# linux_module.net
KiCad netlist of a schematic drawn in Altium Designer
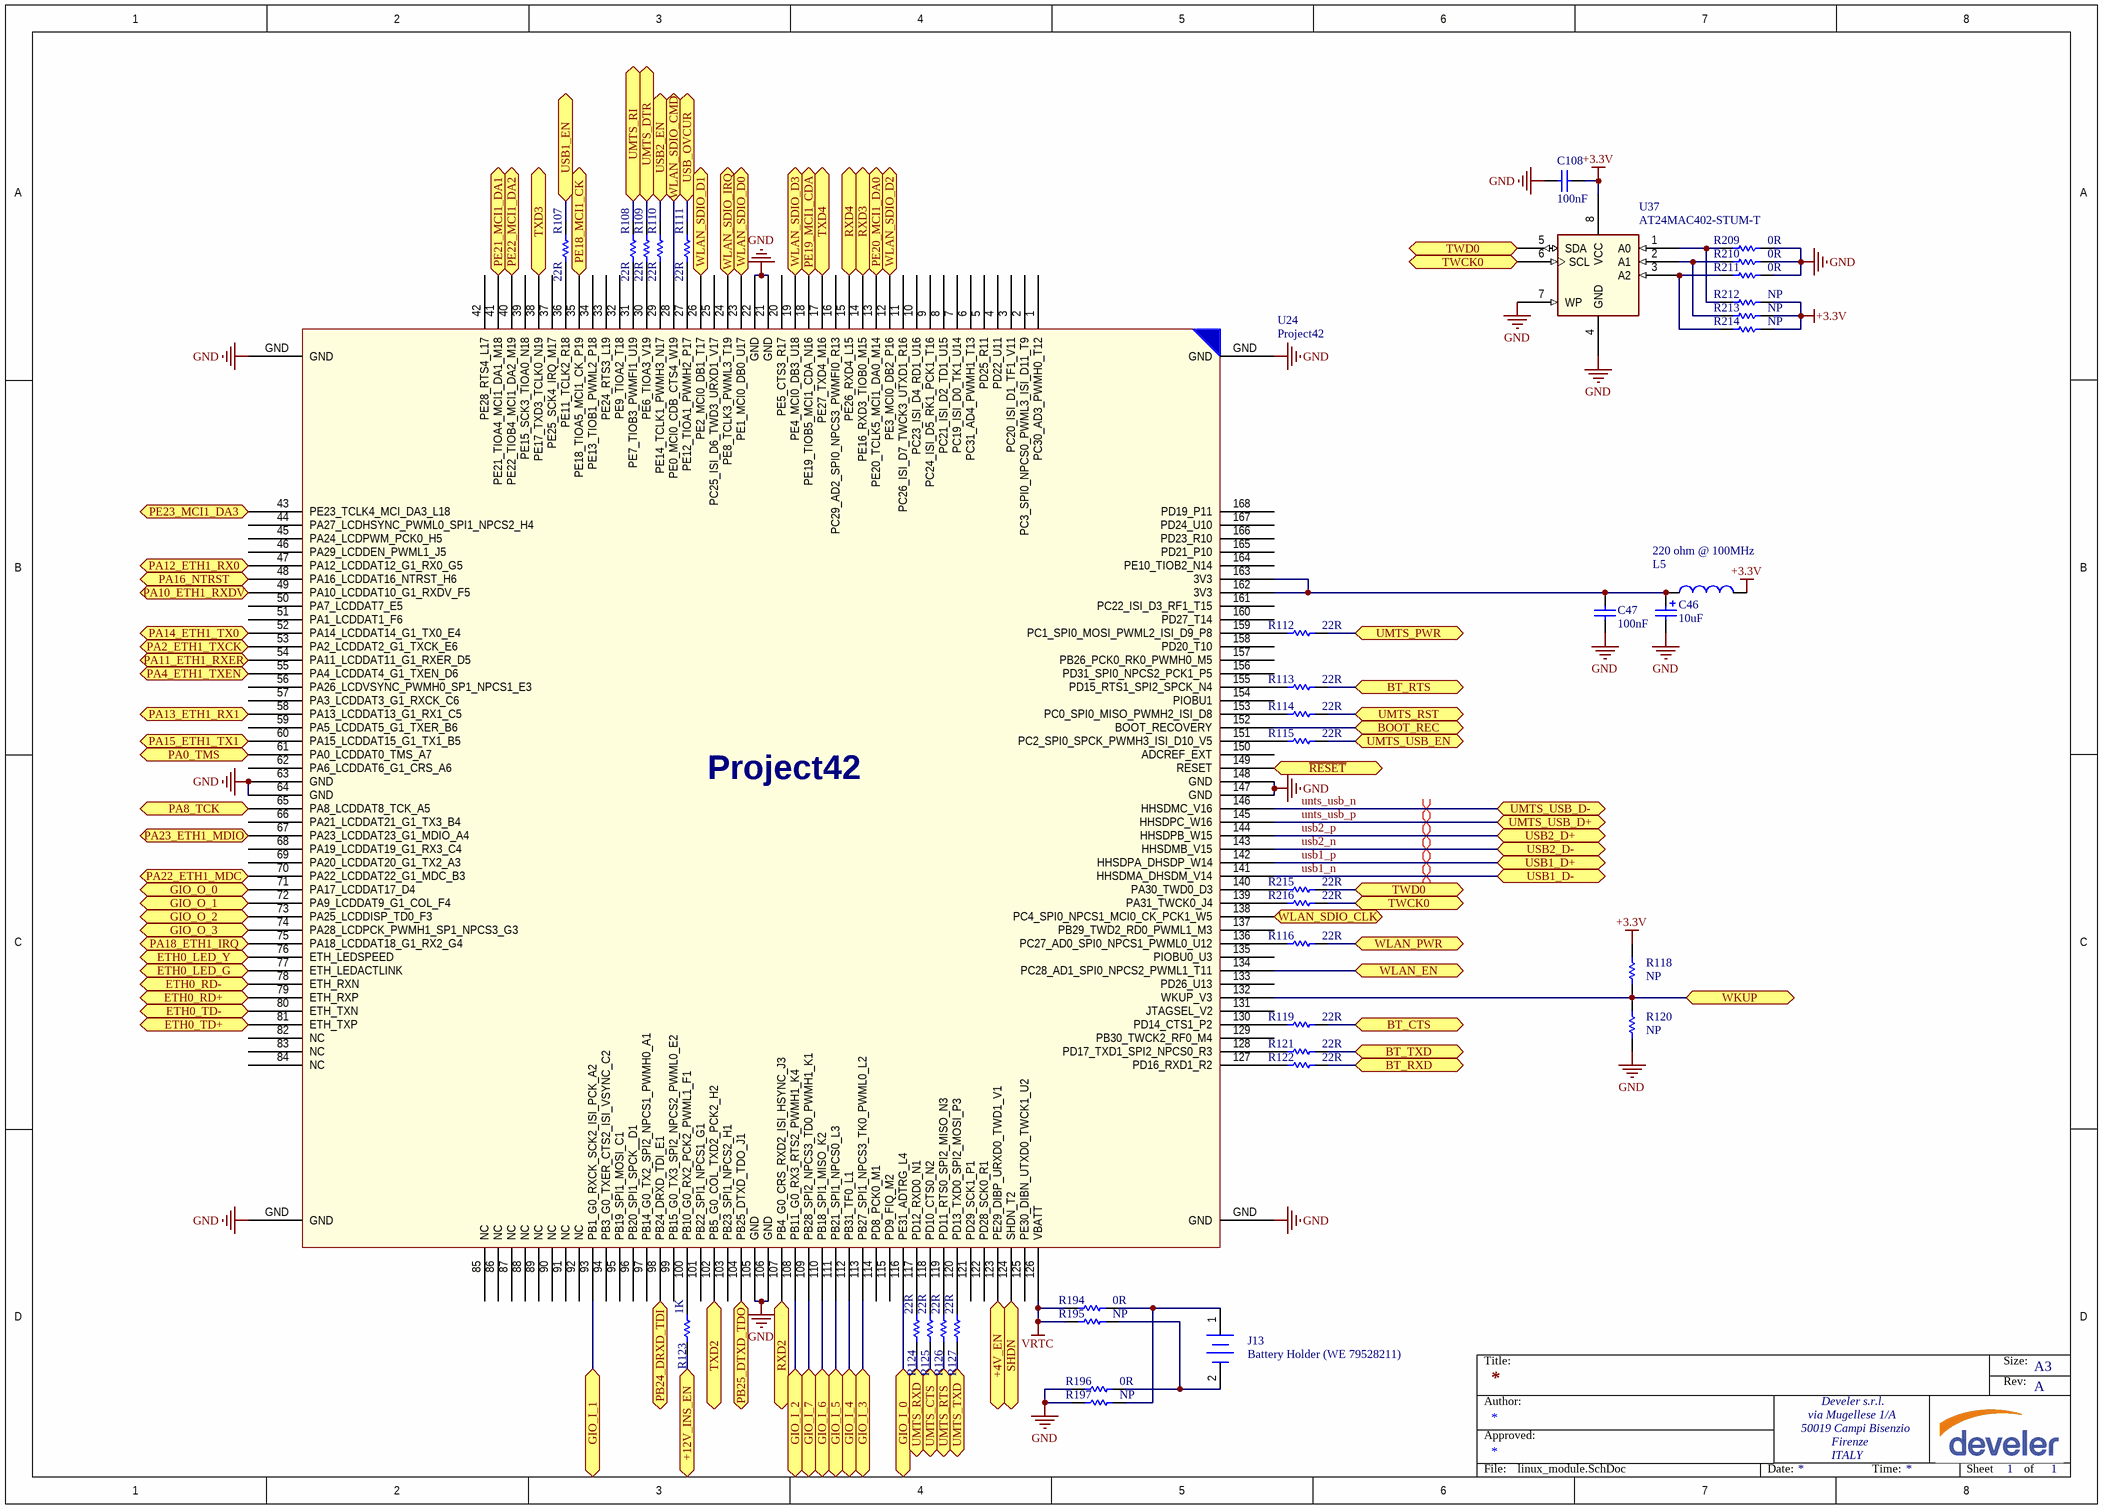
[diagram p0: linux_module.SchDoc]

(export (version "E")
  (design (tool "Eeschema 10.0.6"))
  (components
    (comp (ref "C46")
      (value "10uF")
      (footprint "1206_[3216]")
      (description "Ceramic X5R 25V")
      (fields (field (name "PUBLISHER") "Altium Limited"))
      (libsource (lib "DEVELER_Library") (part "Cap Pol1"))
    )
    (comp (ref "C47")
      (value "100nF")
      (footprint "0603_[1608]")
      (description "Ceramic X7R 50V")
      (fields (field (name "PUBLISHER") "Altium Limited"))
      (libsource (lib "Miscellaneous Devices") (part "Cap"))
    )
    (comp (ref "C108")
      (value "100nF")
      (footprint "0603_[1608]")
      (description "Ceramic X7R 50V")
      (fields (field (name "PUBLISHER") "Altium Limited"))
      (libsource (lib "Miscellaneous Devices") (part "Cap"))
    )
    (comp (ref "J13")
      (value "Battery Holder (WE 79528211)")
      (footprint "Battery_cr2032_holder")
      (description "Multicell Battery CR2032")
      (fields (field (name "PUBLISHER") "Altium Limited"))
      (libsource (lib "Miscellaneous Devices") (part "Battery"))
    )
    (comp (ref "L5")
      (value "220 ohm @ 100MHz")
      (footprint "0805_[2012]")
      (description "WE 742792022")
      (libsource (lib "DEVELER_Library") (part "Inductor"))
    )
    (comp (ref "R107")
      (value "22R")
      (footprint "0603_[1608]")
      (description "Resistor")
      (fields (field (name "PUBLISHER") "Altium Limited"))
      (libsource (lib "DEVELER_Library") (part "Res1"))
    )
    (comp (ref "R108")
      (value "22R")
      (footprint "0603_[1608]")
      (description "Resistor")
      (fields (field (name "PUBLISHER") "Altium Limited"))
      (libsource (lib "DEVELER_Library") (part "Res1"))
    )
    (comp (ref "R109")
      (value "22R")
      (footprint "0603_[1608]")
      (description "Resistor")
      (fields (field (name "PUBLISHER") "Altium Limited"))
      (libsource (lib "DEVELER_Library") (part "Res1"))
    )
    (comp (ref "R110")
      (value "22R")
      (footprint "0603_[1608]")
      (description "Resistor")
      (fields (field (name "PUBLISHER") "Altium Limited"))
      (libsource (lib "DEVELER_Library") (part "Res1"))
    )
    (comp (ref "R111")
      (value "22R")
      (footprint "0603_[1608]")
      (description "Resistor")
      (fields (field (name "PUBLISHER") "Altium Limited"))
      (libsource (lib "DEVELER_Library") (part "Res1"))
    )
    (comp (ref "R112")
      (value "22R")
      (footprint "0603_[1608]")
      (description "Resistor")
      (fields (field (name "PUBLISHER") "Altium Limited"))
      (libsource (lib "DEVELER_Library") (part "Res1"))
    )
    (comp (ref "R113")
      (value "22R")
      (footprint "0603_[1608]")
      (description "Resistor")
      (fields (field (name "PUBLISHER") "Altium Limited"))
      (libsource (lib "DEVELER_Library") (part "Res1"))
    )
    (comp (ref "R114")
      (value "22R")
      (footprint "0603_[1608]")
      (description "Resistor")
      (fields (field (name "PUBLISHER") "Altium Limited"))
      (libsource (lib "DEVELER_Library") (part "Res1"))
    )
    (comp (ref "R115")
      (value "22R")
      (footprint "0603_[1608]")
      (description "Resistor")
      (fields (field (name "PUBLISHER") "Altium Limited"))
      (libsource (lib "DEVELER_Library") (part "Res1"))
    )
    (comp (ref "R116")
      (value "22R")
      (footprint "0603_[1608]")
      (description "Resistor")
      (fields (field (name "PUBLISHER") "Altium Limited"))
      (libsource (lib "DEVELER_Library") (part "Res1"))
    )
    (comp (ref "R118")
      (value "NP")
      (footprint "0603_[1608]")
      (description "Resistor")
      (fields (field (name "PUBLISHER") "Altium Limited"))
      (libsource (lib "DEVELER_Library") (part "Res1"))
    )
    (comp (ref "R119")
      (value "22R")
      (footprint "0603_[1608]")
      (description "Resistor")
      (fields (field (name "PUBLISHER") "Altium Limited"))
      (libsource (lib "DEVELER_Library") (part "Res1"))
    )
    (comp (ref "R120")
      (value "NP")
      (footprint "0603_[1608]")
      (description "Resistor")
      (fields (field (name "PUBLISHER") "Altium Limited"))
      (libsource (lib "DEVELER_Library") (part "Res1"))
    )
    (comp (ref "R121")
      (value "22R")
      (footprint "0603_[1608]")
      (description "Resistor")
      (fields (field (name "PUBLISHER") "Altium Limited"))
      (libsource (lib "DEVELER_Library") (part "Res1"))
    )
    (comp (ref "R122")
      (value "22R")
      (footprint "0603_[1608]")
      (description "Resistor")
      (fields (field (name "PUBLISHER") "Altium Limited"))
      (libsource (lib "DEVELER_Library") (part "Res1"))
    )
    (comp (ref "R123")
      (value "1K")
      (footprint "0603_[1608]")
      (description "Resistor")
      (fields (field (name "PUBLISHER") "Altium Limited"))
      (libsource (lib "DEVELER_Library") (part "Res1"))
    )
    (comp (ref "R124")
      (value "22R")
      (footprint "0603_[1608]")
      (description "Resistor")
      (fields (field (name "PUBLISHER") "Altium Limited"))
      (libsource (lib "DEVELER_Library") (part "Res1"))
    )
    (comp (ref "R125")
      (value "22R")
      (footprint "0603_[1608]")
      (description "Resistor")
      (fields (field (name "PUBLISHER") "Altium Limited"))
      (libsource (lib "DEVELER_Library") (part "Res1"))
    )
    (comp (ref "R126")
      (value "22R")
      (footprint "0603_[1608]")
      (description "Resistor")
      (fields (field (name "PUBLISHER") "Altium Limited"))
      (libsource (lib "DEVELER_Library") (part "Res1"))
    )
    (comp (ref "R127")
      (value "22R")
      (footprint "0603_[1608]")
      (description "Resistor")
      (fields (field (name "PUBLISHER") "Altium Limited"))
      (libsource (lib "DEVELER_Library") (part "Res1"))
    )
    (comp (ref "R194")
      (value "0R")
      (footprint "0603_[1608]")
      (description "Resistor")
      (fields (field (name "PUBLISHER") "Altium Limited"))
      (libsource (lib "DEVELER_Library") (part "Res1"))
    )
    (comp (ref "R195")
      (value "NP")
      (footprint "0603_[1608]")
      (description "Resistor")
      (fields (field (name "PUBLISHER") "Altium Limited"))
      (libsource (lib "DEVELER_Library") (part "Res1"))
    )
    (comp (ref "R196")
      (value "0R")
      (footprint "0603_[1608]")
      (description "Resistor")
      (fields (field (name "PUBLISHER") "Altium Limited"))
      (libsource (lib "DEVELER_Library") (part "Res1"))
    )
    (comp (ref "R197")
      (value "NP")
      (footprint "0603_[1608]")
      (description "Resistor")
      (fields (field (name "PUBLISHER") "Altium Limited"))
      (libsource (lib "DEVELER_Library") (part "Res1"))
    )
    (comp (ref "R209")
      (value "0R")
      (footprint "0603_[1608]")
      (description "Resistor")
      (fields (field (name "PUBLISHER") "Altium Limited"))
      (libsource (lib "DEVELER_Library") (part "Res1"))
    )
    (comp (ref "R210")
      (value "0R")
      (footprint "0603_[1608]")
      (description "Resistor")
      (fields (field (name "PUBLISHER") "Altium Limited"))
      (libsource (lib "DEVELER_Library") (part "Res1"))
    )
    (comp (ref "R211")
      (value "0R")
      (footprint "0603_[1608]")
      (description "Resistor")
      (fields (field (name "PUBLISHER") "Altium Limited"))
      (libsource (lib "DEVELER_Library") (part "Res1"))
    )
    (comp (ref "R212")
      (value "NP")
      (footprint "0603_[1608]")
      (description "Resistor")
      (fields (field (name "PUBLISHER") "Altium Limited"))
      (libsource (lib "DEVELER_Library") (part "Res1"))
    )
    (comp (ref "R213")
      (value "NP")
      (footprint "0603_[1608]")
      (description "Resistor")
      (fields (field (name "PUBLISHER") "Altium Limited"))
      (libsource (lib "DEVELER_Library") (part "Res1"))
    )
    (comp (ref "R214")
      (value "NP")
      (footprint "0603_[1608]")
      (description "Resistor")
      (fields (field (name "PUBLISHER") "Altium Limited"))
      (libsource (lib "DEVELER_Library") (part "Res1"))
    )
    (comp (ref "R215")
      (value "22R")
      (footprint "0603_[1608]")
      (description "Resistor")
      (fields (field (name "PUBLISHER") "Altium Limited"))
      (libsource (lib "DEVELER_Library") (part "Res1"))
    )
    (comp (ref "R216")
      (value "22R")
      (footprint "0603_[1608]")
      (description "Resistor")
      (fields (field (name "PUBLISHER") "Altium Limited"))
      (libsource (lib "DEVELER_Library") (part "Res1"))
    )
    (comp (ref "U24")
      (value "Project42")
      (footprint "project42_footprint")
      (description "Faster Little Linux Module")
      (libsource (lib "project42_lib") (part "project42_pinout"))
    )
    (comp (ref "U37")
      (value "AT24MAC402-STUM-T")
      (footprint "SOIC8")
      (description "EEPROM MAC 48bit EUI + Serial (AT24MAC602-STUM-T for 64bit EUI)")
      (libsource (lib "DEVELER_Library") (part "EEPROM-SOIC8"))
    )
  )
  (nets
    (net (code "1") (name "+3.3V") (class "Default")
      (node (ref "C108") (pin "1") (pinfunction "1_1") (pintype "passive"))
      (node (ref "L5") (pin "1") (pinfunction "1_1") (pintype "passive"))
      (node (ref "R118") (pin "2") (pinfunction "2_2") (pintype "passive"))
      (node (ref "R212") (pin "1") (pinfunction "1_1") (pintype "passive"))
      (node (ref "R213") (pin "1") (pinfunction "1_1") (pintype "passive"))
      (node (ref "R214") (pin "1") (pinfunction "1_1") (pintype "passive"))
      (node (ref "U37") (pin "8") (pinfunction "VCC_8") (pintype "power_in"))
    )
    (net (code "2") (name "/+4V_EN") (class "Default")
      (node (ref "U24") (pin "123") (pinfunction "PE29_DIBP_URXD0_TWD1_V1_123") (pintype "passive"))
    )
    (net (code "3") (name "/+12V_INS_EN") (class "Default")
      (node (ref "R123") (pin "1") (pinfunction "1_1") (pintype "passive"))
    )
    (net (code "4") (name "/BOOT_REC") (class "Default")
      (node (ref "U24") (pin "152") (pinfunction "BOOT_RECOVERY_152") (pintype "passive"))
    )
    (net (code "5") (name "/BT_CTS") (class "Default")
      (node (ref "R119") (pin "1") (pinfunction "1_1") (pintype "passive"))
    )
    (net (code "6") (name "/BT_RTS") (class "Default")
      (node (ref "R113") (pin "1") (pinfunction "1_1") (pintype "passive"))
    )
    (net (code "7") (name "/BT_RXD") (class "Default")
      (node (ref "R122") (pin "1") (pinfunction "1_1") (pintype "passive"))
    )
    (net (code "8") (name "/BT_TXD") (class "Default")
      (node (ref "R121") (pin "1") (pinfunction "1_1") (pintype "passive"))
    )
    (net (code "9") (name "/ETH0_LED_G") (class "Default")
      (node (ref "U24") (pin "77") (pinfunction "ETH_LEDACTLINK_77") (pintype "passive"))
    )
    (net (code "10") (name "/ETH0_LED_Y") (class "Default")
      (node (ref "U24") (pin "76") (pinfunction "ETH_LEDSPEED_76") (pintype "passive"))
    )
    (net (code "11") (name "/ETH0_RD+") (class "Default")
      (node (ref "U24") (pin "79") (pinfunction "ETH_RXP_79") (pintype "passive"))
    )
    (net (code "12") (name "/ETH0_RD-") (class "Default")
      (node (ref "U24") (pin "78") (pinfunction "ETH_RXN_78") (pintype "passive"))
    )
    (net (code "13") (name "/ETH0_TD+") (class "Default")
      (node (ref "U24") (pin "81") (pinfunction "ETH_TXP_81") (pintype "passive"))
    )
    (net (code "14") (name "/ETH0_TD-") (class "Default")
      (node (ref "U24") (pin "80") (pinfunction "ETH_TXN_80") (pintype "passive"))
    )
    (net (code "15") (name "/GIO_I_0") (class "Default")
      (node (ref "U24") (pin "116") (pinfunction "PE31_ADTRG_L4_116") (pintype "passive"))
    )
    (net (code "16") (name "/GIO_I_1") (class "Default")
      (node (ref "U24") (pin "93") (pinfunction "PB1_G0_RXCK_SCK2_ISI_PCK_A2_93") (pintype "passive"))
    )
    (net (code "17") (name "/GIO_I_2") (class "Default")
      (node (ref "U24") (pin "108") (pinfunction "PB11_G0_RX3_RTS2_PWMH1_K4_108") (pintype "passive"))
    )
    (net (code "18") (name "/GIO_I_3") (class "Default")
      (node (ref "U24") (pin "113") (pinfunction "PB27_SPI1_NPCS3_TK0_PWML0_L2_113") (pintype "passive"))
    )
    (net (code "19") (name "/GIO_I_4") (class "Default")
      (node (ref "U24") (pin "112") (pinfunction "PB31_TF0_L1_112") (pintype "passive"))
    )
    (net (code "20") (name "/GIO_I_5") (class "Default")
      (node (ref "U24") (pin "111") (pinfunction "PB21_SPI1_NPCS0_L3_111") (pintype "passive"))
    )
    (net (code "21") (name "/GIO_I_6") (class "Default")
      (node (ref "U24") (pin "110") (pinfunction "PB18_SPI1_MISO_K2_110") (pintype "passive"))
    )
    (net (code "22") (name "/GIO_I_7") (class "Default")
      (node (ref "U24") (pin "109") (pinfunction "PB28_SPI2_NPCS3_TD0_PWMH1_K1_109") (pintype "passive"))
    )
    (net (code "23") (name "/GIO_O_0") (class "Default")
      (node (ref "U24") (pin "71") (pinfunction "PA17_LCDDAT17_D4_71") (pintype "passive"))
    )
    (net (code "24") (name "/GIO_O_1") (class "Default")
      (node (ref "U24") (pin "72") (pinfunction "PA9_LCDDAT9_G1_COL_F4_72") (pintype "passive"))
    )
    (net (code "25") (name "/GIO_O_2") (class "Default")
      (node (ref "U24") (pin "73") (pinfunction "PA25_LCDDISP_TD0_F3_73") (pintype "passive"))
    )
    (net (code "26") (name "/GIO_O_3") (class "Default")
      (node (ref "U24") (pin "74") (pinfunction "PA28_LCDPCK_PWMH1_SP1_NPCS3_G3_74") (pintype "passive"))
    )
    (net (code "27") (name "/PA0_TMS") (class "Default")
      (node (ref "U24") (pin "61") (pinfunction "PA0_LCDDAT0_TMS_A7_61") (pintype "passive"))
    )
    (net (code "28") (name "/PA2_ETH1_TXCK") (class "Default")
      (node (ref "U24") (pin "53") (pinfunction "PA2_LCDDAT2_G1_TXCK_E6_53") (pintype "passive"))
    )
    (net (code "29") (name "/PA4_ETH1_TXEN") (class "Default")
      (node (ref "U24") (pin "55") (pinfunction "PA4_LCDDAT4_G1_TXEN_D6_55") (pintype "passive"))
    )
    (net (code "30") (name "/PA8_TCK") (class "Default")
      (node (ref "U24") (pin "65") (pinfunction "PA8_LCDDAT8_TCK_A5_65") (pintype "passive"))
    )
    (net (code "31") (name "/PA10_ETH1_RXDV") (class "Default")
      (node (ref "U24") (pin "49") (pinfunction "PA10_LCDDAT10_G1_RXDV_F5_49") (pintype "passive"))
    )
    (net (code "32") (name "/PA11_ETH1_RXER") (class "Default")
      (node (ref "U24") (pin "54") (pinfunction "PA11_LCDDAT11_G1_RXER_D5_54") (pintype "passive"))
    )
    (net (code "33") (name "/PA12_ETH1_RX0") (class "Default")
      (node (ref "U24") (pin "47") (pinfunction "PA12_LCDDAT12_G1_RX0_G5_47") (pintype "passive"))
    )
    (net (code "34") (name "/PA13_ETH1_RX1") (class "Default")
      (node (ref "U24") (pin "58") (pinfunction "PA13_LCDDAT13_G1_RX1_C5_58") (pintype "passive"))
    )
    (net (code "35") (name "/PA14_ETH1_TX0") (class "Default")
      (node (ref "U24") (pin "52") (pinfunction "PA14_LCDDAT14_G1_TX0_E4_52") (pintype "passive"))
    )
    (net (code "36") (name "/PA15_ETH1_TX1") (class "Default")
      (node (ref "U24") (pin "60") (pinfunction "PA15_LCDDAT15_G1_TX1_B5_60") (pintype "passive"))
    )
    (net (code "37") (name "/PA16_NTRST") (class "Default")
      (node (ref "U24") (pin "48") (pinfunction "PA16_LCDDAT16_NTRST_H6_48") (pintype "passive"))
    )
    (net (code "38") (name "/PA18_ETH1_IRQ") (class "Default")
      (node (ref "U24") (pin "75") (pinfunction "PA18_LCDDAT18_G1_RX2_G4_75") (pintype "passive"))
    )
    (net (code "39") (name "/PA22_ETH1_MDC") (class "Default")
      (node (ref "U24") (pin "70") (pinfunction "PA22_LCDDAT22_G1_MDC_B3_70") (pintype "passive"))
    )
    (net (code "40") (name "/PA23_ETH1_MDIO") (class "Default")
      (node (ref "U24") (pin "67") (pinfunction "PA23_LCDDAT23_G1_MDIO_A4_67") (pintype "passive"))
    )
    (net (code "41") (name "/PB24_DRXD_TDI") (class "Default")
      (node (ref "U24") (pin "98") (pinfunction "PB24_DRXD_TDI_E1_98") (pintype "passive"))
    )
    (net (code "42") (name "/PB25_DTXD_TDO") (class "Default")
      (node (ref "U24") (pin "104") (pinfunction "PB25_DTXD_TDO_J1_104") (pintype "passive"))
    )
    (net (code "48") (name "/PE18_MCI1_CK") (class "Default")
      (node (ref "U24") (pin "35") (pinfunction "PE18_TIOA5_MCI1_CK_P19_35") (pintype "passive"))
    )
    (net (code "50") (name "/PE19_MCI1_CDA") (class "Default")
      (node (ref "U24") (pin "18") (pinfunction "PE19_TIOB5_MCI1_CDA_N16_18") (pintype "passive"))
    )
    (net (code "53") (name "/PE20_MCI1_DA0") (class "Default")
      (node (ref "U24") (pin "13") (pinfunction "PE20_TCLK5_MCI1_DA0_M14_13") (pintype "passive"))
    )
    (net (code "54") (name "/PE21_MCI1_DA1") (class "Default")
      (node (ref "U24") (pin "41") (pinfunction "PE21_TIOA4_MCI1_DA1_M18_41") (pintype "passive"))
    )
    (net (code "55") (name "/PE22_MCI1_DA2") (class "Default")
      (node (ref "U24") (pin "40") (pinfunction "PE22_TIOB4_MCI1_DA2_M19_40") (pintype "passive"))
    )
    (net (code "56") (name "/PE23_MCI1_DA3") (class "Default")
      (node (ref "U24") (pin "43") (pinfunction "PE23_TCLK4_MCI_DA3_L18_43") (pintype "passive"))
    )
    (net (code "59") (name "/RXD2") (class "Default")
      (node (ref "U24") (pin "107") (pinfunction "PB4_G0_CRS_RXD2_ISI_HSYNC_J3_107") (pintype "passive"))
    )
    (net (code "60") (name "/RXD3") (class "Default")
      (node (ref "U24") (pin "14") (pinfunction "PE16_RXD3_TIOB0_M15_14") (pintype "passive"))
    )
    (net (code "61") (name "/RXD4") (class "Default")
      (node (ref "U24") (pin "15") (pinfunction "PE26_RXD4_L15_15") (pintype "passive"))
    )
    (net (code "62") (name "/SHDN") (class "Default")
      (node (ref "U24") (pin "124") (pinfunction "SHDN_T2_124") (pintype "passive"))
    )
    (net (code "63") (name "/TWCK0") (class "Default")
      (node (ref "R216") (pin "1") (pinfunction "1_1") (pintype "passive"))
      (node (ref "U37") (pin "6") (pinfunction "SCL_6") (pintype "input"))
    )
    (net (code "64") (name "/TWD0") (class "Default")
      (node (ref "R215") (pin "1") (pinfunction "1_1") (pintype "passive"))
      (node (ref "U37") (pin "5") (pinfunction "SDA_5") (pintype "bidirectional"))
    )
    (net (code "65") (name "/TXD2") (class "Default")
      (node (ref "U24") (pin "102") (pinfunction "PB5_G0_COL_TXD2_PCK2_H2_102") (pintype "passive"))
    )
    (net (code "66") (name "/TXD3") (class "Default")
      (node (ref "U24") (pin "38") (pinfunction "PE17_TXD3_TCLK0_N19_38") (pintype "passive"))
    )
    (net (code "67") (name "/TXD4") (class "Default")
      (node (ref "U24") (pin "17") (pinfunction "PE27_TXD4_M16_17") (pintype "passive"))
    )
    (net (code "68") (name "/UMTS_CTS") (class "Default")
      (node (ref "R125") (pin "1") (pinfunction "1_1") (pintype "passive"))
    )
    (net (code "69") (name "/UMTS_DTR") (class "Default")
      (node (ref "R109") (pin "1") (pinfunction "1_1") (pintype "passive"))
    )
    (net (code "70") (name "/UMTS_PWR") (class "Default")
      (node (ref "R112") (pin "1") (pinfunction "1_1") (pintype "passive"))
    )
    (net (code "71") (name "/UMTS_RI") (class "Default")
      (node (ref "R108") (pin "1") (pinfunction "1_1") (pintype "passive"))
    )
    (net (code "72") (name "/UMTS_RST") (class "Default")
      (node (ref "R114") (pin "1") (pinfunction "1_1") (pintype "passive"))
    )
    (net (code "73") (name "/UMTS_RTS") (class "Default")
      (node (ref "R126") (pin "1") (pinfunction "1_1") (pintype "passive"))
    )
    (net (code "75") (name "/UMTS_RXD") (class "Default")
      (node (ref "R124") (pin "1") (pinfunction "1_1") (pintype "passive"))
    )
    (net (code "81") (name "/UMTS_TXD") (class "Default")
      (node (ref "R127") (pin "1") (pinfunction "1_1") (pintype "passive"))
    )
    (net (code "82") (name "/UMTS_USB_EN") (class "Default")
      (node (ref "R115") (pin "1") (pinfunction "1_1") (pintype "passive"))
    )
    (net (code "83") (name "/USB1_EN") (class "Default")
      (node (ref "R107") (pin "1") (pinfunction "1_1") (pintype "passive"))
    )
    (net (code "84") (name "/USB2_EN") (class "Default")
      (node (ref "R110") (pin "1") (pinfunction "1_1") (pintype "passive"))
    )
    (net (code "85") (name "/USB_OVCUR") (class "Default")
      (node (ref "R111") (pin "1") (pinfunction "1_1") (pintype "passive"))
    )
    (net (code "86") (name "/WKUP") (class "Default")
      (node (ref "R118") (pin "1") (pinfunction "1_1") (pintype "passive"))
      (node (ref "R120") (pin "2") (pinfunction "2_2") (pintype "passive"))
      (node (ref "U24") (pin "132") (pinfunction "WKUP_V3_132") (pintype "passive"))
    )
    (net (code "87") (name "/WLAN_EN") (class "Default")
      (node (ref "U24") (pin "134") (pinfunction "PC28_AD1_SPI0_NPCS2_PWML1_T11_134") (pintype "passive"))
    )
    (net (code "88") (name "/WLAN_PWR") (class "Default")
      (node (ref "R116") (pin "1") (pinfunction "1_1") (pintype "passive"))
    )
    (net (code "89") (name "/WLAN_SDIO_CLK") (class "Default")
      (node (ref "U24") (pin "138") (pinfunction "PC4_SPI0_NPCS1_MCI0_CK_PCK1_W5_138") (pintype "passive"))
    )
    (net (code "90") (name "/WLAN_SDIO_CMD") (class "Default")
      (node (ref "U24") (pin "28") (pinfunction "PE0_MCI0_CDB_CTS4_W19_28") (pintype "passive"))
    )
    (net (code "91") (name "/WLAN_SDIO_D0") (class "Default")
      (node (ref "U24") (pin "23") (pinfunction "PE1_MCI0_DB0_U17_23") (pintype "passive"))
    )
    (net (code "92") (name "/WLAN_SDIO_D1") (class "Default")
      (node (ref "U24") (pin "26") (pinfunction "PE2_MCI0_DB1_T17_26") (pintype "passive"))
    )
    (net (code "93") (name "/WLAN_SDIO_D2") (class "Default")
      (node (ref "U24") (pin "12") (pinfunction "PE3_MCI0_DB2_P16_12") (pintype "passive"))
    )
    (net (code "94") (name "/WLAN_SDIO_D3") (class "Default")
      (node (ref "U24") (pin "19") (pinfunction "PE4_MCI0_DB3_U18_19") (pintype "passive"))
    )
    (net (code "95") (name "/WLAN_SDIO_IRQ") (class "Default")
      (node (ref "U24") (pin "24") (pinfunction "PE8_TCLK3_PWML3_T19_24") (pintype "passive"))
    )
    (net (code "96") (name "/unts_usb_n") (class "Default")
      (node (ref "U24") (pin "146") (pinfunction "HHSDMC_V16_146") (pintype "passive"))
    )
    (net (code "97") (name "/unts_usb_p") (class "Default")
      (node (ref "U24") (pin "145") (pinfunction "HHSDPC_W16_145") (pintype "passive"))
    )
    (net (code "98") (name "/usb1_n") (class "Default")
      (node (ref "U24") (pin "141") (pinfunction "HHSDMA_DHSDM_V14_141") (pintype "passive"))
    )
    (net (code "99") (name "/usb1_p") (class "Default")
      (node (ref "U24") (pin "142") (pinfunction "HHSDPA_DHSDP_W14_142") (pintype "passive"))
    )
    (net (code "100") (name "/usb2_n") (class "Default")
      (node (ref "U24") (pin "143") (pinfunction "HHSDMB_V15_143") (pintype "passive"))
    )
    (net (code "101") (name "/usb2_p") (class "Default")
      (node (ref "U24") (pin "144") (pinfunction "HHSDPB_W15_144") (pintype "passive"))
    )
    (net (code "102") (name "/~{RESET}") (class "Default")
      (node (ref "U24") (pin "149") (pinfunction "RESET_149") (pintype "passive"))
    )
    (net (code "103") (name "GND") (class "Default")
      (node (ref "C108") (pin "2") (pinfunction "2_2") (pintype "passive"))
      (node (ref "C46") (pin "2") (pinfunction "2_2") (pintype "passive"))
      (node (ref "C47") (pin "2") (pinfunction "2_2") (pintype "passive"))
      (node (ref "R120") (pin "1") (pinfunction "1_1") (pintype "passive"))
      (node (ref "R196") (pin "2") (pinfunction "2_2") (pintype "passive"))
      (node (ref "R197") (pin "2") (pinfunction "2_2") (pintype "passive"))
      (node (ref "R209") (pin "1") (pinfunction "1_1") (pintype "passive"))
      (node (ref "R210") (pin "1") (pinfunction "1_1") (pintype "passive"))
      (node (ref "R211") (pin "1") (pinfunction "1_1") (pintype "passive"))
      (node (ref "U24") (pin "105") (pinfunction "GND_105") (pintype "passive"))
      (node (ref "U24") (pin "106") (pinfunction "GND_106") (pintype "passive"))
      (node (ref "U24") (pin "147") (pinfunction "GND_147") (pintype "passive"))
      (node (ref "U24") (pin "148") (pinfunction "GND_148") (pintype "passive"))
      (node (ref "U24") (pin "21") (pinfunction "GND_21") (pintype "passive"))
      (node (ref "U24") (pin "22") (pinfunction "GND_22") (pintype "passive"))
      (node (ref "U24") (pin "63") (pinfunction "GND_63") (pintype "passive"))
      (node (ref "U24") (pin "64") (pinfunction "GND_64") (pintype "passive"))
      (node (ref "U24") (pin "GND") (pinfunction "GND_GND") (pintype "passive"))
      (node (ref "U37") (pin "4") (pinfunction "GND_4") (pintype "power_in"))
      (node (ref "U37") (pin "7") (pinfunction "WP_7") (pintype "input"))
    )
    (net (code "104") (name "Net-(C46-Pad1)") (class "Default")
      (node (ref "C46") (pin "1") (pinfunction "1_1") (pintype "passive"))
      (node (ref "C47") (pin "1") (pinfunction "1_1") (pintype "passive"))
      (node (ref "L5") (pin "2") (pinfunction "2_2") (pintype "passive"))
      (node (ref "U24") (pin "162") (pinfunction "3V3_162") (pintype "passive"))
      (node (ref "U24") (pin "163") (pinfunction "3V3_163") (pintype "passive"))
    )
    (net (code "105") (name "Net-(J13-+)") (class "Default")
      (node (ref "J13") (pin "1") (pinfunction "+_1") (pintype "passive"))
      (node (ref "R194") (pin "1") (pinfunction "1_1") (pintype "passive"))
      (node (ref "R197") (pin "1") (pinfunction "1_1") (pintype "passive"))
    )
    (net (code "106") (name "Net-(J13--)") (class "Default")
      (node (ref "J13") (pin "2") (pinfunction "-_2") (pintype "passive"))
      (node (ref "R195") (pin "1") (pinfunction "1_1") (pintype "passive"))
      (node (ref "R196") (pin "1") (pinfunction "1_1") (pintype "passive"))
    )
    (net (code "107") (name "Net-(U24-PA30_TWD0_D3)") (class "Default")
      (node (ref "R215") (pin "2") (pinfunction "2_2") (pintype "passive"))
      (node (ref "U24") (pin "140") (pinfunction "PA30_TWD0_D3_140") (pintype "passive"))
    )
    (net (code "108") (name "Net-(U24-PA31_TWCK0_J4)") (class "Default")
      (node (ref "R216") (pin "2") (pinfunction "2_2") (pintype "passive"))
      (node (ref "U24") (pin "139") (pinfunction "PA31_TWCK0_J4_139") (pintype "passive"))
    )
    (net (code "109") (name "Net-(U24-PB10_G0_RX2_PCK2_PWML1_F1)") (class "Default")
      (node (ref "R123") (pin "2") (pinfunction "2_2") (pintype "passive"))
      (node (ref "U24") (pin "100") (pinfunction "PB10_G0_RX2_PCK2_PWML1_F1_100") (pintype "passive"))
    )
    (net (code "110") (name "Net-(U24-PC0_SPI0_MISO_PWMH2_ISI_D8)") (class "Default")
      (node (ref "R114") (pin "2") (pinfunction "2_2") (pintype "passive"))
      (node (ref "U24") (pin "153") (pinfunction "PC0_SPI0_MISO_PWMH2_ISI_D8_153") (pintype "passive"))
    )
    (net (code "111") (name "Net-(U24-PC1_SPI0_MOSI_PWML2_ISI_D9_P8)") (class "Default")
      (node (ref "R112") (pin "2") (pinfunction "2_2") (pintype "passive"))
      (node (ref "U24") (pin "159") (pinfunction "PC1_SPI0_MOSI_PWML2_ISI_D9_P8_159") (pintype "passive"))
    )
    (net (code "112") (name "Net-(U24-PC2_SPI0_SPCK_PWMH3_ISI_D10_V5)") (class "Default")
      (node (ref "R115") (pin "2") (pinfunction "2_2") (pintype "passive"))
      (node (ref "U24") (pin "151") (pinfunction "PC2_SPI0_SPCK_PWMH3_ISI_D10_V5_151") (pintype "passive"))
    )
    (net (code "113") (name "Net-(U24-PC27_AD0_SPI0_NPCS1_PWML0_U12)") (class "Default")
      (node (ref "R116") (pin "2") (pinfunction "2_2") (pintype "passive"))
      (node (ref "U24") (pin "136") (pinfunction "PC27_AD0_SPI0_NPCS1_PWML0_U12_136") (pintype "passive"))
    )
    (net (code "114") (name "Net-(U24-PD10_CTS0_N2)") (class "Default")
      (node (ref "R125") (pin "2") (pinfunction "2_2") (pintype "passive"))
      (node (ref "U24") (pin "118") (pinfunction "PD10_CTS0_N2_118") (pintype "passive"))
    )
    (net (code "115") (name "Net-(U24-PD11_RTS0_SPI2_MISO_N3)") (class "Default")
      (node (ref "R126") (pin "2") (pinfunction "2_2") (pintype "passive"))
      (node (ref "U24") (pin "119") (pinfunction "PD11_RTS0_SPI2_MISO_N3_119") (pintype "passive"))
    )
    (net (code "116") (name "Net-(U24-PD12_RXD0_N1)") (class "Default")
      (node (ref "R124") (pin "2") (pinfunction "2_2") (pintype "passive"))
      (node (ref "U24") (pin "117") (pinfunction "PD12_RXD0_N1_117") (pintype "passive"))
    )
    (net (code "117") (name "Net-(U24-PD13_TXD0_SPI2_MOSI_P3)") (class "Default")
      (node (ref "R127") (pin "2") (pinfunction "2_2") (pintype "passive"))
      (node (ref "U24") (pin "120") (pinfunction "PD13_TXD0_SPI2_MOSI_P3_120") (pintype "passive"))
    )
    (net (code "118") (name "Net-(U24-PD14_CTS1_P2)") (class "Default")
      (node (ref "R119") (pin "2") (pinfunction "2_2") (pintype "passive"))
      (node (ref "U24") (pin "130") (pinfunction "PD14_CTS1_P2_130") (pintype "passive"))
    )
    (net (code "119") (name "Net-(U24-PD15_RTS1_SPI2_SPCK_N4)") (class "Default")
      (node (ref "R113") (pin "2") (pinfunction "2_2") (pintype "passive"))
      (node (ref "U24") (pin "155") (pinfunction "PD15_RTS1_SPI2_SPCK_N4_155") (pintype "passive"))
    )
    (net (code "120") (name "Net-(U24-PD16_RXD1_R2)") (class "Default")
      (node (ref "R122") (pin "2") (pinfunction "2_2") (pintype "passive"))
      (node (ref "U24") (pin "127") (pinfunction "PD16_RXD1_R2_127") (pintype "passive"))
    )
    (net (code "121") (name "Net-(U24-PD17_TXD1_SPI2_NPCS0_R3)") (class "Default")
      (node (ref "R121") (pin "2") (pinfunction "2_2") (pintype "passive"))
      (node (ref "U24") (pin "128") (pinfunction "PD17_TXD1_SPI2_NPCS0_R3_128") (pintype "passive"))
    )
    (net (code "122") (name "Net-(U24-PE6_TIOA3_V19)") (class "Default")
      (node (ref "R109") (pin "2") (pinfunction "2_2") (pintype "passive"))
      (node (ref "U24") (pin "30") (pinfunction "PE6_TIOA3_V19_30") (pintype "passive"))
    )
    (net (code "123") (name "Net-(U24-PE7_TIOB3_PWMFI1_U19)") (class "Default")
      (node (ref "R108") (pin "2") (pinfunction "2_2") (pintype "passive"))
      (node (ref "U24") (pin "31") (pinfunction "PE7_TIOB3_PWMFI1_U19_31") (pintype "passive"))
    )
    (net (code "124") (name "Net-(U24-PE11_TCLK2_R18)") (class "Default")
      (node (ref "R107") (pin "2") (pinfunction "2_2") (pintype "passive"))
      (node (ref "U24") (pin "36") (pinfunction "PE11_TCLK2_R18_36") (pintype "passive"))
    )
    (net (code "125") (name "Net-(U24-PE12_TIOA1_PWMH2_P17)") (class "Default")
      (node (ref "R111") (pin "2") (pinfunction "2_2") (pintype "passive"))
      (node (ref "U24") (pin "27") (pinfunction "PE12_TIOA1_PWMH2_P17_27") (pintype "passive"))
    )
    (net (code "126") (name "Net-(U24-PE14_TCLK1_PWMH3_N17)") (class "Default")
      (node (ref "R110") (pin "2") (pinfunction "2_2") (pintype "passive"))
      (node (ref "U24") (pin "29") (pinfunction "PE14_TCLK1_PWMH3_N17_29") (pintype "passive"))
    )
    (net (code "127") (name "Net-(U37-A0)") (class "Default")
      (node (ref "R209") (pin "2") (pinfunction "2_2") (pintype "passive"))
      (node (ref "R212") (pin "2") (pinfunction "2_2") (pintype "passive"))
      (node (ref "U37") (pin "1") (pinfunction "A0_1") (pintype "input"))
    )
    (net (code "128") (name "Net-(U37-A1)") (class "Default")
      (node (ref "R210") (pin "2") (pinfunction "2_2") (pintype "passive"))
      (node (ref "R213") (pin "2") (pinfunction "2_2") (pintype "passive"))
      (node (ref "U37") (pin "2") (pinfunction "A1_2") (pintype "input"))
    )
    (net (code "129") (name "Net-(U37-A2)") (class "Default")
      (node (ref "R211") (pin "2") (pinfunction "2_2") (pintype "passive"))
      (node (ref "R214") (pin "2") (pinfunction "2_2") (pintype "passive"))
      (node (ref "U37") (pin "3") (pinfunction "A2_3") (pintype "input"))
    )
    (net (code "130") (name "VRTC") (class "Default")
      (node (ref "R194") (pin "2") (pinfunction "2_2") (pintype "passive"))
      (node (ref "R195") (pin "2") (pinfunction "2_2") (pintype "passive"))
      (node (ref "U24") (pin "126") (pinfunction "VBATT_126") (pintype "passive"))
    )
    (net (code "131") (name "unconnected-(U24-ADCREF_EXT-Pad150)") (class "Default")
      (node (ref "U24") (pin "150") (pinfunction "ADCREF_EXT_150") (pintype "passive"))
    )
    (net (code "132") (name "unconnected-(U24-JTAGSEL_V2-Pad131)") (class "Default")
      (node (ref "U24") (pin "131") (pinfunction "JTAGSEL_V2_131") (pintype "passive"))
    )
    (net (code "133") (name "unconnected-(U24-NC-Pad82)") (class "Default")
      (node (ref "U24") (pin "82") (pinfunction "NC_82") (pintype "passive"))
    )
    (net (code "134") (name "unconnected-(U24-NC-Pad83)") (class "Default")
      (node (ref "U24") (pin "83") (pinfunction "NC_83") (pintype "passive"))
    )
    (net (code "135") (name "unconnected-(U24-NC-Pad84)") (class "Default")
      (node (ref "U24") (pin "84") (pinfunction "NC_84") (pintype "passive"))
    )
    (net (code "136") (name "unconnected-(U24-NC-Pad85)") (class "Default")
      (node (ref "U24") (pin "85") (pinfunction "NC_85") (pintype "passive"))
    )
    (net (code "137") (name "unconnected-(U24-NC-Pad86)") (class "Default")
      (node (ref "U24") (pin "86") (pinfunction "NC_86") (pintype "passive"))
    )
    (net (code "138") (name "unconnected-(U24-NC-Pad87)") (class "Default")
      (node (ref "U24") (pin "87") (pinfunction "NC_87") (pintype "passive"))
    )
    (net (code "139") (name "unconnected-(U24-NC-Pad88)") (class "Default")
      (node (ref "U24") (pin "88") (pinfunction "NC_88") (pintype "passive"))
    )
    (net (code "140") (name "unconnected-(U24-NC-Pad89)") (class "Default")
      (node (ref "U24") (pin "89") (pinfunction "NC_89") (pintype "passive"))
    )
    (net (code "141") (name "unconnected-(U24-NC-Pad90)") (class "Default")
      (node (ref "U24") (pin "90") (pinfunction "NC_90") (pintype "passive"))
    )
    (net (code "142") (name "unconnected-(U24-NC-Pad91)") (class "Default")
      (node (ref "U24") (pin "91") (pinfunction "NC_91") (pintype "passive"))
    )
    (net (code "143") (name "unconnected-(U24-NC-Pad92)") (class "Default")
      (node (ref "U24") (pin "92") (pinfunction "NC_92") (pintype "passive"))
    )
    (net (code "144") (name "unconnected-(U24-PA1_LCDDAT1_F6-Pad51)") (class "Default")
      (node (ref "U24") (pin "51") (pinfunction "PA1_LCDDAT1_F6_51") (pintype "passive"))
    )
    (net (code "145") (name "unconnected-(U24-PA3_LCDDAT3_G1_RXCK_C6-Pad57)") (class "Default")
      (node (ref "U24") (pin "57") (pinfunction "PA3_LCDDAT3_G1_RXCK_C6_57") (pintype "passive"))
    )
    (net (code "146") (name "unconnected-(U24-PA5_LCDDAT5_G1_TXER_B6-Pad59)") (class "Default")
      (node (ref "U24") (pin "59") (pinfunction "PA5_LCDDAT5_G1_TXER_B6_59") (pintype "passive"))
    )
    (net (code "147") (name "unconnected-(U24-PA6_LCDDAT6_G1_CRS_A6-Pad62)") (class "Default")
      (node (ref "U24") (pin "62") (pinfunction "PA6_LCDDAT6_G1_CRS_A6_62") (pintype "passive"))
    )
    (net (code "148") (name "unconnected-(U24-PA7_LCDDAT7_E5-Pad50)") (class "Default")
      (node (ref "U24") (pin "50") (pinfunction "PA7_LCDDAT7_E5_50") (pintype "passive"))
    )
    (net (code "149") (name "unconnected-(U24-PA19_LCDDAT19_G1_RX3_C4-Pad68)") (class "Default")
      (node (ref "U24") (pin "68") (pinfunction "PA19_LCDDAT19_G1_RX3_C4_68") (pintype "passive"))
    )
    (net (code "150") (name "unconnected-(U24-PA20_LCDDAT20_G1_TX2_A3-Pad69)") (class "Default")
      (node (ref "U24") (pin "69") (pinfunction "PA20_LCDDAT20_G1_TX2_A3_69") (pintype "passive"))
    )
    (net (code "151") (name "unconnected-(U24-PA21_LCDDAT21_G1_TX3_B4-Pad66)") (class "Default")
      (node (ref "U24") (pin "66") (pinfunction "PA21_LCDDAT21_G1_TX3_B4_66") (pintype "passive"))
    )
    (net (code "152") (name "unconnected-(U24-PA24_LCDPWM_PCK0_H5-Pad45)") (class "Default")
      (node (ref "U24") (pin "45") (pinfunction "PA24_LCDPWM_PCK0_H5_45") (pintype "passive"))
    )
    (net (code "153") (name "unconnected-(U24-PA26_LCDVSYNC_PWMH0_SP1_NPCS1_E3-Pad56)") (class "Default")
      (node (ref "U24") (pin "56") (pinfunction "PA26_LCDVSYNC_PWMH0_SP1_NPCS1_E3_56") (pintype "passive"))
    )
    (net (code "154") (name "unconnected-(U24-PA27_LCDHSYNC_PWML0_SPI1_NPCS2_H4-Pad44)") (class "Default")
      (node (ref "U24") (pin "44") (pinfunction "PA27_LCDHSYNC_PWML0_SPI1_NPCS2_H4_44") (pintype "passive"))
    )
    (net (code "155") (name "unconnected-(U24-PA29_LCDDEN_PWML1_J5-Pad46)") (class "Default")
      (node (ref "U24") (pin "46") (pinfunction "PA29_LCDDEN_PWML1_J5_46") (pintype "passive"))
    )
    (net (code "156") (name "unconnected-(U24-PB3_G0_TXER_CTS2_ISI_VSYNC_C2-Pad94)") (class "Default")
      (node (ref "U24") (pin "94") (pinfunction "PB3_G0_TXER_CTS2_ISI_VSYNC_C2_94") (pintype "passive"))
    )
    (net (code "157") (name "unconnected-(U24-PB14_G0_TX2_SPI2_NPCS1_PWMH0_A1-Pad97)") (class "Default")
      (node (ref "U24") (pin "97") (pinfunction "PB14_G0_TX2_SPI2_NPCS1_PWMH0_A1_97") (pintype "passive"))
    )
    (net (code "158") (name "unconnected-(U24-PB15_G0_TX3_SPI2_NPCS2_PWML0_E2-Pad99)") (class "Default")
      (node (ref "U24") (pin "99") (pinfunction "PB15_G0_TX3_SPI2_NPCS2_PWML0_E2_99") (pintype "passive"))
    )
    (net (code "159") (name "unconnected-(U24-PB19_SPI1_MOSI_C1-Pad95)") (class "Default")
      (node (ref "U24") (pin "95") (pinfunction "PB19_SPI1_MOSI_C1_95") (pintype "passive"))
    )
    (net (code "160") (name "unconnected-(U24-PB20_SPI1_SPCK__D1-Pad96)") (class "Default")
      (node (ref "U24") (pin "96") (pinfunction "PB20_SPI1_SPCK__D1_96") (pintype "passive"))
    )
    (net (code "161") (name "unconnected-(U24-PB22_SPI1_NPCS1_G1-Pad101)") (class "Default")
      (node (ref "U24") (pin "101") (pinfunction "PB22_SPI1_NPCS1_G1_101") (pintype "passive"))
    )
    (net (code "162") (name "unconnected-(U24-PB23_SPI1_NPCS2_H1-Pad103)") (class "Default")
      (node (ref "U24") (pin "103") (pinfunction "PB23_SPI1_NPCS2_H1_103") (pintype "passive"))
    )
    (net (code "163") (name "unconnected-(U24-PB26_PCK0_RK0_PWMH0_M5-Pad157)") (class "Default")
      (node (ref "U24") (pin "157") (pinfunction "PB26_PCK0_RK0_PWMH0_M5_157") (pintype "passive"))
    )
    (net (code "164") (name "unconnected-(U24-PB29_TWD2_RD0_PWML1_M3-Pad137)") (class "Default")
      (node (ref "U24") (pin "137") (pinfunction "PB29_TWD2_RD0_PWML1_M3_137") (pintype "passive"))
    )
    (net (code "165") (name "unconnected-(U24-PB30_TWCK2_RF0_M4-Pad129)") (class "Default")
      (node (ref "U24") (pin "129") (pinfunction "PB30_TWCK2_RF0_M4_129") (pintype "passive"))
    )
    (net (code "166") (name "unconnected-(U24-PC3_SPI0_NPCS0_PWML3_ISI_D11_T9-Pad2)") (class "Default")
      (node (ref "U24") (pin "2") (pinfunction "PC3_SPI0_NPCS0_PWML3_ISI_D11_T9_2") (pintype "passive"))
    )
    (net (code "167") (name "unconnected-(U24-PC19_ISI_D0_TK1_U14-Pad7)") (class "Default")
      (node (ref "U24") (pin "7") (pinfunction "PC19_ISI_D0_TK1_U14_7") (pintype "passive"))
    )
    (net (code "168") (name "unconnected-(U24-PC20_ISI_D1_TF1_V11-Pad3)") (class "Default")
      (node (ref "U24") (pin "3") (pinfunction "PC20_ISI_D1_TF1_V11_3") (pintype "passive"))
    )
    (net (code "169") (name "unconnected-(U24-PC21_ISI_D2_TD1_U15-Pad8)") (class "Default")
      (node (ref "U24") (pin "8") (pinfunction "PC21_ISI_D2_TD1_U15_8") (pintype "passive"))
    )
    (net (code "170") (name "unconnected-(U24-PC22_ISI_D3_RF1_T15-Pad161)") (class "Default")
      (node (ref "U24") (pin "161") (pinfunction "PC22_ISI_D3_RF1_T15_161") (pintype "passive"))
    )
    (net (code "171") (name "unconnected-(U24-PC23_ISI_D4_RD1_U16-Pad10)") (class "Default")
      (node (ref "U24") (pin "10") (pinfunction "PC23_ISI_D4_RD1_U16_10") (pintype "passive"))
    )
    (net (code "172") (name "unconnected-(U24-PC24_ISI_D5_RK1_PCK1_T16-Pad9)") (class "Default")
      (node (ref "U24") (pin "9") (pinfunction "PC24_ISI_D5_RK1_PCK1_T16_9") (pintype "passive"))
    )
    (net (code "173") (name "unconnected-(U24-PC25_ISI_D6_TWD3_URXD1_V17-Pad25)") (class "Default")
      (node (ref "U24") (pin "25") (pinfunction "PC25_ISI_D6_TWD3_URXD1_V17_25") (pintype "passive"))
    )
    (net (code "174") (name "unconnected-(U24-PC26_ISI_D7_TWCK3_UTXD1_R16-Pad11)") (class "Default")
      (node (ref "U24") (pin "11") (pinfunction "PC26_ISI_D7_TWCK3_UTXD1_R16_11") (pintype "passive"))
    )
    (net (code "175") (name "unconnected-(U24-PC29_AD2_SPI0_NPCS3_PWMFI0_R13-Pad16)") (class "Default")
      (node (ref "U24") (pin "16") (pinfunction "PC29_AD2_SPI0_NPCS3_PWMFI0_R13_16") (pintype "passive"))
    )
    (net (code "176") (name "unconnected-(U24-PC30_AD3_PWMH0_T12-Pad1)") (class "Default")
      (node (ref "U24") (pin "1") (pinfunction "PC30_AD3_PWMH0_T12_1") (pintype "passive"))
    )
    (net (code "177") (name "unconnected-(U24-PC31_AD4_PWMH1_T13-Pad6)") (class "Default")
      (node (ref "U24") (pin "6") (pinfunction "PC31_AD4_PWMH1_T13_6") (pintype "passive"))
    )
    (net (code "178") (name "unconnected-(U24-PD8_PCK0_M1-Pad114)") (class "Default")
      (node (ref "U24") (pin "114") (pinfunction "PD8_PCK0_M1_114") (pintype "passive"))
    )
    (net (code "179") (name "unconnected-(U24-PD9_FIQ_M2-Pad115)") (class "Default")
      (node (ref "U24") (pin "115") (pinfunction "PD9_FIQ_M2_115") (pintype "passive"))
    )
    (net (code "180") (name "unconnected-(U24-PD19_P11-Pad168)") (class "Default")
      (node (ref "U24") (pin "168") (pinfunction "PD19_P11_168") (pintype "passive"))
    )
    (net (code "181") (name "unconnected-(U24-PD20_T10-Pad158)") (class "Default")
      (node (ref "U24") (pin "158") (pinfunction "PD20_T10_158") (pintype "passive"))
    )
    (net (code "182") (name "unconnected-(U24-PD21_P10-Pad165)") (class "Default")
      (node (ref "U24") (pin "165") (pinfunction "PD21_P10_165") (pintype "passive"))
    )
    (net (code "183") (name "unconnected-(U24-PD22_U11-Pad4)") (class "Default")
      (node (ref "U24") (pin "4") (pinfunction "PD22_U11_4") (pintype "passive"))
    )
    (net (code "184") (name "unconnected-(U24-PD23_R10-Pad166)") (class "Default")
      (node (ref "U24") (pin "166") (pinfunction "PD23_R10_166") (pintype "passive"))
    )
    (net (code "185") (name "unconnected-(U24-PD24_U10-Pad167)") (class "Default")
      (node (ref "U24") (pin "167") (pinfunction "PD24_U10_167") (pintype "passive"))
    )
    (net (code "186") (name "unconnected-(U24-PD25_R11-Pad5)") (class "Default")
      (node (ref "U24") (pin "5") (pinfunction "PD25_R11_5") (pintype "passive"))
    )
    (net (code "187") (name "unconnected-(U24-PD26_U13-Pad133)") (class "Default")
      (node (ref "U24") (pin "133") (pinfunction "PD26_U13_133") (pintype "passive"))
    )
    (net (code "188") (name "unconnected-(U24-PD27_T14-Pad160)") (class "Default")
      (node (ref "U24") (pin "160") (pinfunction "PD27_T14_160") (pintype "passive"))
    )
    (net (code "189") (name "unconnected-(U24-PD28_SCK0_R1-Pad122)") (class "Default")
      (node (ref "U24") (pin "122") (pinfunction "PD28_SCK0_R1_122") (pintype "passive"))
    )
    (net (code "190") (name "unconnected-(U24-PD29_SCK1_P1-Pad121)") (class "Default")
      (node (ref "U24") (pin "121") (pinfunction "PD29_SCK1_P1_121") (pintype "passive"))
    )
    (net (code "191") (name "unconnected-(U24-PD31_SPI0_NPCS2_PCK1_P5-Pad156)") (class "Default")
      (node (ref "U24") (pin "156") (pinfunction "PD31_SPI0_NPCS2_PCK1_P5_156") (pintype "passive"))
    )
    (net (code "192") (name "unconnected-(U24-PE5_CTS3_R17-Pad20)") (class "Default")
      (node (ref "U24") (pin "20") (pinfunction "PE5_CTS3_R17_20") (pintype "passive"))
    )
    (net (code "193") (name "unconnected-(U24-PE9_TIOA2_T18-Pad32)") (class "Default")
      (node (ref "U24") (pin "32") (pinfunction "PE9_TIOA2_T18_32") (pintype "passive"))
    )
    (net (code "194") (name "unconnected-(U24-PE10_TIOB2_N14-Pad164)") (class "Default")
      (node (ref "U24") (pin "164") (pinfunction "PE10_TIOB2_N14_164") (pintype "passive"))
    )
    (net (code "195") (name "unconnected-(U24-PE13_TIOB1_PWML2_P18-Pad34)") (class "Default")
      (node (ref "U24") (pin "34") (pinfunction "PE13_TIOB1_PWML2_P18_34") (pintype "passive"))
    )
    (net (code "196") (name "unconnected-(U24-PE15_SCK3_TIOA0_N18-Pad39)") (class "Default")
      (node (ref "U24") (pin "39") (pinfunction "PE15_SCK3_TIOA0_N18_39") (pintype "passive"))
    )
    (net (code "197") (name "unconnected-(U24-PE24_RTS3_L19-Pad33)") (class "Default")
      (node (ref "U24") (pin "33") (pinfunction "PE24_RTS3_L19_33") (pintype "passive"))
    )
    (net (code "198") (name "unconnected-(U24-PE25_SCK4_IRQ_M17-Pad37)") (class "Default")
      (node (ref "U24") (pin "37") (pinfunction "PE25_SCK4_IRQ_M17_37") (pintype "passive"))
    )
    (net (code "199") (name "unconnected-(U24-PE28_RTS4_L17-Pad42)") (class "Default")
      (node (ref "U24") (pin "42") (pinfunction "PE28_RTS4_L17_42") (pintype "passive"))
    )
    (net (code "200") (name "unconnected-(U24-PE30_DIBN_UTXD0_TWCK1_U2-Pad125)") (class "Default")
      (node (ref "U24") (pin "125") (pinfunction "PE30_DIBN_UTXD0_TWCK1_U2_125") (pintype "passive"))
    )
    (net (code "201") (name "unconnected-(U24-PIOBU0_U3-Pad135)") (class "Default")
      (node (ref "U24") (pin "135") (pinfunction "PIOBU0_U3_135") (pintype "passive"))
    )
    (net (code "202") (name "unconnected-(U24-PIOBU1-Pad154)") (class "Default")
      (node (ref "U24") (pin "154") (pinfunction "PIOBU1_154") (pintype "passive"))
    )
  )
)
